# watersensor.net
KiCad netlist of a schematic drawn in EAGLE
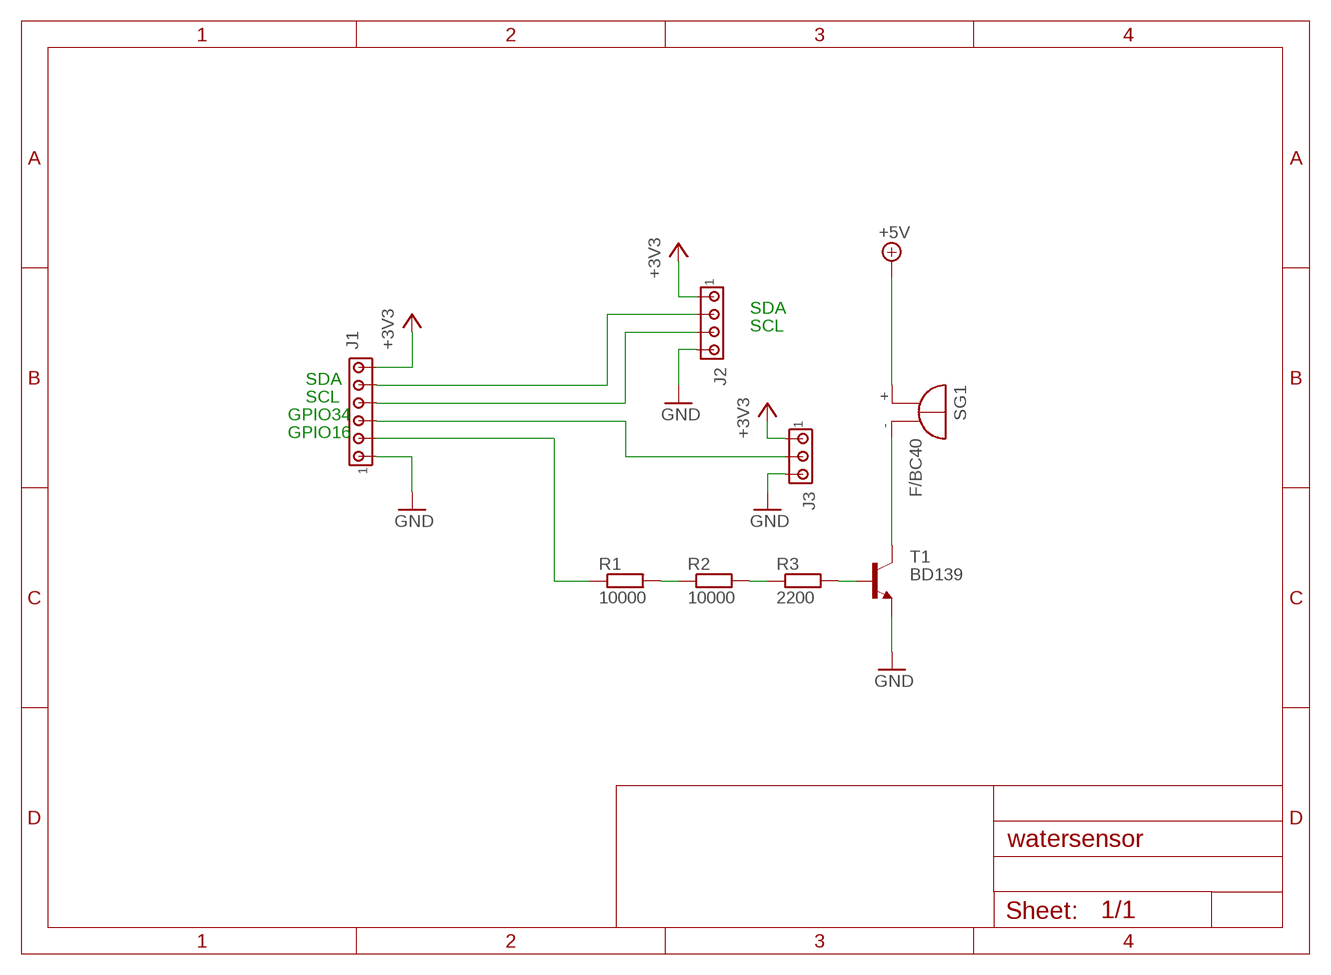
[diagram p0: schematic, sheet 1]

(export (version "E")
  (design (tool "Eeschema 10.0.6"))
  (components
    (comp (ref "J1")
      (value "MTA06-100")
      (footprint "eagle-import:10X06MTA")
      (libsource (lib "eagle-import") (part "MTA06-100"))
    )
    (comp (ref "J2")
      (value "MTA04-100")
      (footprint "eagle-import:10X04MTA")
      (libsource (lib "eagle-import") (part "MTA04-100"))
    )
    (comp (ref "J3")
      (value "MTA03-100")
      (footprint "eagle-import:10X03MTA")
      (libsource (lib "eagle-import") (part "MTA03-100"))
    )
    (comp (ref "R1")
      (value "10000")
      (footprint "eagle-import:0204_7")
      (libsource (lib "eagle-import") (part "R-EU_0204/7"))
    )
    (comp (ref "R2")
      (value "10000")
      (footprint "eagle-import:0204_7")
      (libsource (lib "eagle-import") (part "R-EU_0204/7"))
    )
    (comp (ref "R3")
      (value "2200")
      (footprint "eagle-import:0204_7")
      (libsource (lib "eagle-import") (part "R-EU_0204/7"))
    )
    (comp (ref "SG1")
      (value "F/BC40")
      (footprint "eagle-import:F_BC40")
      (libsource (lib "eagle-import") (part "F/BC40"))
    )
    (comp (ref "T1")
      (value "BD139")
      (footprint "eagle-import:TO126")
      (libsource (lib "eagle-import") (part "BD139"))
    )
  )
  (nets
    (net (code "1") (name "+3V3") (class "Default")
      (node (ref "J1") (pin "6") (pinfunction "6_6") (pintype "passive"))
      (node (ref "J2") (pin "1") (pinfunction "1_1") (pintype "passive"))
      (node (ref "J3") (pin "1") (pinfunction "1_1") (pintype "passive"))
    )
    (net (code "2") (name "+5V") (class "Default")
      (node (ref "SG1") (pin "+") (pinfunction "+_+") (pintype "passive"))
    )
    (net (code "3") (name "GND") (class "Default")
      (node (ref "J1") (pin "1") (pinfunction "1_1") (pintype "passive"))
      (node (ref "J2") (pin "4") (pinfunction "4_4") (pintype "passive"))
      (node (ref "J3") (pin "3") (pinfunction "3_3") (pintype "passive"))
      (node (ref "T1") (pin "1") (pinfunction "E_1") (pintype "passive"))
    )
    (net (code "4") (name "Net-(J1-Pad2)") (class "Default")
      (node (ref "J1") (pin "2") (pinfunction "2_2") (pintype "passive"))
      (node (ref "R1") (pin "1") (pinfunction "1_1") (pintype "passive"))
    )
    (net (code "5") (name "Net-(J1-Pad3)") (class "Default")
      (node (ref "J1") (pin "3") (pinfunction "3_3") (pintype "passive"))
      (node (ref "J3") (pin "2") (pinfunction "2_2") (pintype "passive"))
    )
    (net (code "6") (name "Net-(J1-Pad4)") (class "Default")
      (node (ref "J1") (pin "4") (pinfunction "4_4") (pintype "passive"))
      (node (ref "J2") (pin "3") (pinfunction "3_3") (pintype "passive"))
    )
    (net (code "7") (name "Net-(J1-Pad5)") (class "Default")
      (node (ref "J1") (pin "5") (pinfunction "5_5") (pintype "passive"))
      (node (ref "J2") (pin "2") (pinfunction "2_2") (pintype "passive"))
    )
    (net (code "8") (name "Net-(R1-Pad2)") (class "Default")
      (node (ref "R1") (pin "2") (pinfunction "2_2") (pintype "passive"))
      (node (ref "R2") (pin "1") (pinfunction "1_1") (pintype "passive"))
    )
    (net (code "9") (name "Net-(R2-Pad2)") (class "Default")
      (node (ref "R2") (pin "2") (pinfunction "2_2") (pintype "passive"))
      (node (ref "R3") (pin "1") (pinfunction "1_1") (pintype "passive"))
    )
    (net (code "10") (name "Net-(T1-B)") (class "Default")
      (node (ref "R3") (pin "2") (pinfunction "2_2") (pintype "passive"))
      (node (ref "T1") (pin "3") (pinfunction "B_3") (pintype "passive"))
    )
    (net (code "11") (name "Net-(T1-C)") (class "Default")
      (node (ref "SG1") (pin "-") (pinfunction "-_-") (pintype "passive"))
      (node (ref "T1") (pin "2") (pinfunction "C_2") (pintype "passive"))
    )
  )
)
